# CONNECTORS.net
KiCad netlist of a schematic drawn in Altium Designer
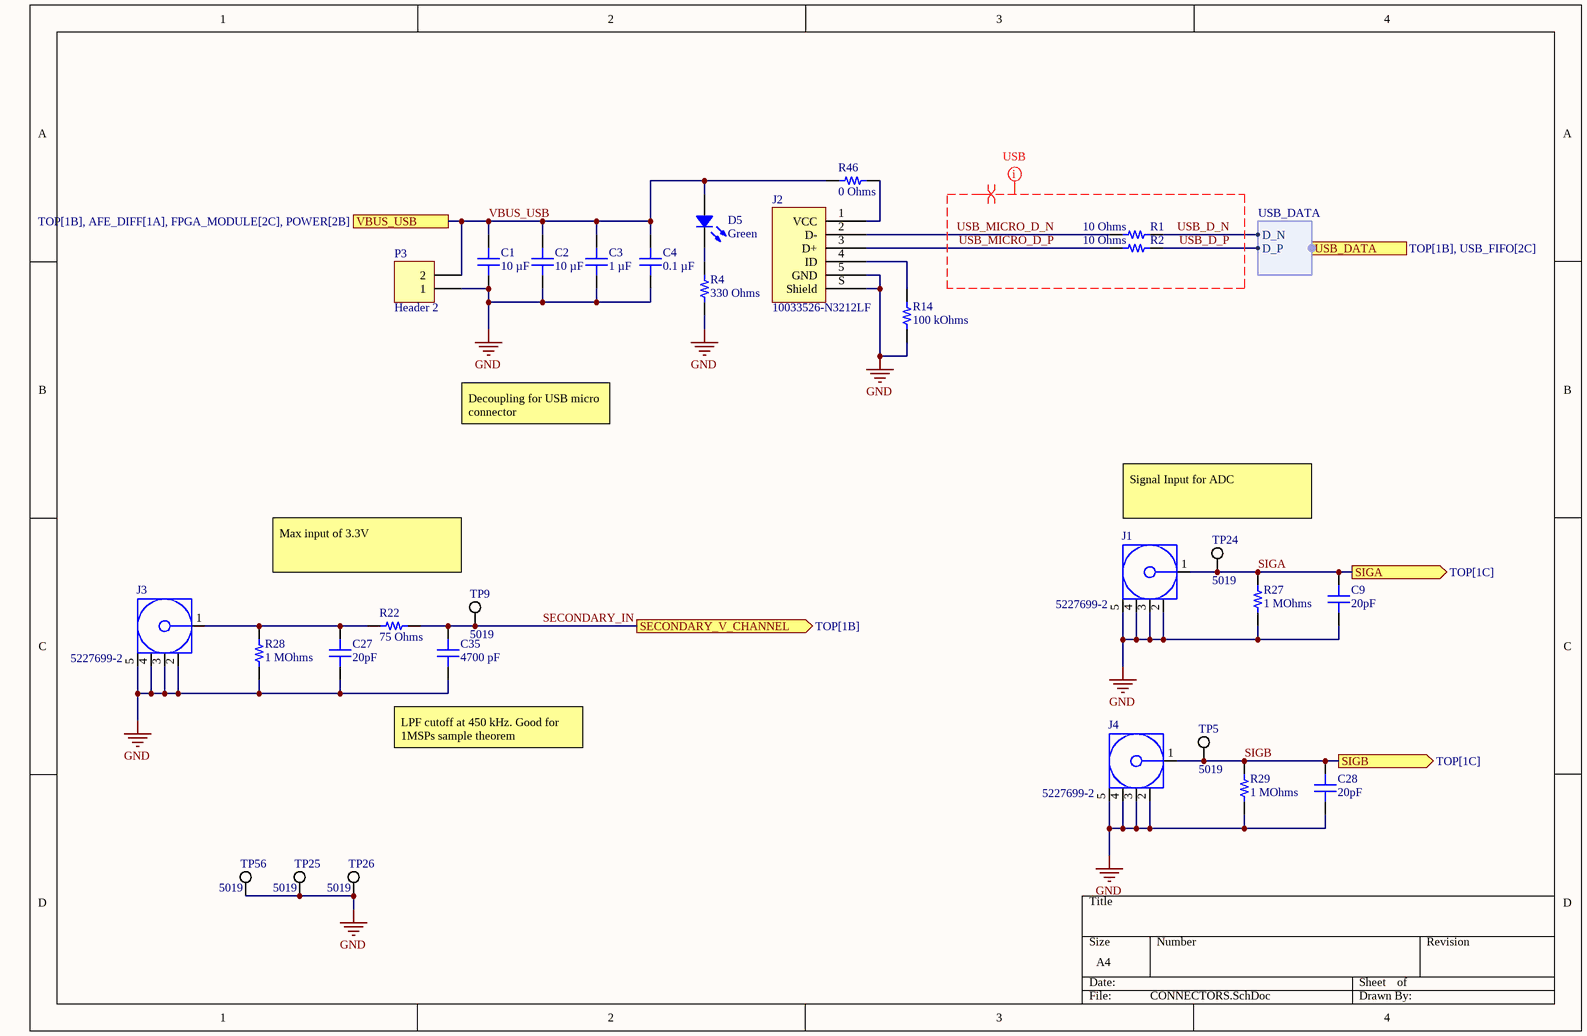
[diagram p0: CONNECTORS.SchDoc]

(export (version "E")
  (design (tool "Eeschema 10.0.6"))
  (components
    (comp (ref "C1")
      (value "10 µF")
      (footprint "CAP 0402_1005")
      (description "CAP CER 10UF 10V X5R 0402")
      (fields
        (field (name "PART NUMBER") "CL05A106MP8NUB8")
        (field (name "MANUFACTURER") "Samsung Electro-Mechanics")
      )
      (libsource (lib "Celestial") (part "Capacitor"))
    )
    (comp (ref "C2")
      (value "10 µF")
      (footprint "CAP 0402_1005")
      (description "CAP CER 10UF 10V X5R 0402")
      (fields
        (field (name "PART NUMBER") "CL05A106MP8NUB8")
        (field (name "MANUFACTURER") "Samsung Electro-Mechanics")
      )
      (libsource (lib "Celestial") (part "Capacitor"))
    )
    (comp (ref "C3")
      (value "1 µF")
      (footprint "CAP 0402_1005")
      (description "CAP CER 1UF 10V X7S 0402")
      (fields
        (field (name "PART NUMBER") "GRM155C71A105KE11D")
        (field (name "MANUFACTURER") "Murata Electronics")
      )
      (libsource (lib "Celestial") (part "Capacitor"))
    )
    (comp (ref "C4")
      (value "0.1 µF")
      (footprint "CAP 0402_1005")
      (description "CAP CER 0.1UF 50V X5R 0402")
      (fields
        (field (name "PART NUMBER") "CGA2B3X5R1H104M050BB")
        (field (name "MANUFACTURER") "TDK Corporation")
      )
      (libsource (lib "Celestial") (part "Capacitor"))
    )
    (comp (ref "C9")
      (value "20pF")
      (footprint "CAP 0402_1005")
      (description "CAP CER 20PF 25V NP0 0402")
      (fields (field (name "PART NUMBER") "04023U200JAT2A") (field (name "MANUFACTURER") "AVX Corporation"))
      (libsource (lib "Celestial") (part "Capacitor"))
    )
    (comp (ref "C27")
      (value "20pF")
      (footprint "CAP 0402_1005")
      (description "CAP CER 20PF 25V NP0 0402")
      (fields (field (name "PART NUMBER") "04023U200JAT2A") (field (name "MANUFACTURER") "AVX Corporation"))
      (libsource (lib "Celestial") (part "Capacitor"))
    )
    (comp (ref "C28")
      (value "20pF")
      (footprint "CAP 0402_1005")
      (description "CAP CER 20PF 25V NP0 0402")
      (fields (field (name "PART NUMBER") "04023U200JAT2A") (field (name "MANUFACTURER") "AVX Corporation"))
      (libsource (lib "Celestial") (part "Capacitor"))
    )
    (comp (ref "C35")
      (value "4700 pF")
      (footprint "CAP 0603_1608")
      (description "CAP CER 0603 4.7NF 16V X7R 10%")
      (fields (field (name "PART NUMBER") "C0603C472K4RECAUTO") (field (name "MANUFACTURER") "KEMET"))
      (libsource (lib "Celestial") (part "Capacitor"))
    )
    (comp (ref "D5")
      (value "Green")
      (footprint "LED 1206_3216 GREEN")
      (description "LED SMD")
      (fields (field (name "PART NUMBER") "APTL3216ZGCK-01") (field (name "MANUFACTURER") "Kingbright"))
      (libsource (lib "Celestial") (part "LED"))
    )
    (comp (ref "J1")
      (value "5227699-2")
      (footprint "TECO-5227699-2_V")
      (description "Jack BNC Connector, 1 Position, Height 16.26 mm, Tail Length 6.35 mm, -55 to 85 degC, RoHS, Tube")
      (fields (field (name "MANUFACTURER") "TE Connectivity"))
      (libsource (lib "Altium Content Vault") (part "CN-S-4F-RF5"))
    )
    (comp (ref "J2")
      (value "10033526-N3212LF")
      (footprint "FCI USB 10033526-N3212LF")
      (description "CONN RCPT MINI USB B 5POS SMD RA")
      (fields (field (name "MANUFACTURER") "Amphenol ICC (FCI)"))
      (libsource (lib "Celestial") (part "USB 2.0 Type B Micro"))
    )
    (comp (ref "J3")
      (value "5227699-2")
      (footprint "TECO-5227699-2_V")
      (description "Jack BNC Connector, 1 Position, Height 16.26 mm, Tail Length 6.35 mm, -55 to 85 degC, RoHS, Tube")
      (fields (field (name "MANUFACTURER") "TE Connectivity"))
      (libsource (lib "Altium Content Vault") (part "CN-S-4F-RF5"))
    )
    (comp (ref "J4")
      (value "5227699-2")
      (footprint "TECO-5227699-2_V")
      (description "Jack BNC Connector, 1 Position, Height 16.26 mm, Tail Length 6.35 mm, -55 to 85 degC, RoHS, Tube")
      (fields (field (name "MANUFACTURER") "TE Connectivity"))
      (libsource (lib "Altium Content Vault") (part "CN-S-4F-RF5"))
    )
    (comp (ref "P3")
      (value "Header 2")
      (footprint "HDR1X2")
      (description "Header, 2-Pin")
      (fields (field (name "PUBLISHER") "Altium Limited"))
      (libsource (lib "Miscellaneous Connectors") (part "Header 2"))
    )
    (comp (ref "R1")
      (value "10 Ohms")
      (footprint "RES 0603_1608")
      (description "RES SMD 10 OHM 0.1% 1/10W 0603")
      (fields (field (name "PART NUMBER") "CRT0603-BY-10R0ELF") (field (name "MANUFACTURER") "Bourns Inc."))
      (libsource (lib "Celestial") (part "Resistor"))
    )
    (comp (ref "R2")
      (value "10 Ohms")
      (footprint "RES 0603_1608")
      (description "RES SMD 10 OHM 0.1% 1/10W 0603")
      (fields (field (name "PART NUMBER") "CRT0603-BY-10R0ELF") (field (name "MANUFACTURER") "Bourns Inc."))
      (libsource (lib "Celestial") (part "Resistor"))
    )
    (comp (ref "R4")
      (value "330 Ohms")
      (footprint "RES 0402_1005")
      (description "RES SMD 330 OHM 5% 1/16W 0402")
      (fields (field (name "PART NUMBER") "AC0402JR-07330RL") (field (name "MANUFACTURER") "Yageo"))
      (libsource (lib "Celestial") (part "Resistor"))
    )
    (comp (ref "R14")
      (value "100 kOhms")
      (footprint "RES 0402_1005")
      (description "RES SMD 100K OHM 0.1% 1/16W 0402")
      (fields
        (field (name "PART NUMBER") "CPF0402B100KE")
        (field (name "MANUFACTURER") "TE Connectivity Passive Product")
      )
      (libsource (lib "Celestial") (part "Resistor"))
    )
    (comp (ref "R22")
      (value "75 Ohms")
      (footprint "RES 0603_1608")
      (description "RES SMD 75 OHM 1% 1/10W 0603")
      (fields (field (name "PART NUMBER") "AC0603FR-0775RL") (field (name "MANUFACTURER") "Yageo"))
      (libsource (lib "Celestial") (part "Resistor"))
    )
    (comp (ref "R27")
      (value "1 MOhms")
      (footprint "RES 0402_1005")
      (description "RES 1M OHM 1% 1/16W 0402")
      (fields
        (field (name "PART NUMBER") "RMCF0402FT1M00")
        (field (name "MANUFACTURER") "Stackpole Electronics Inc")
      )
      (libsource (lib "Celestial") (part "Resistor"))
    )
    (comp (ref "R28")
      (value "1 MOhms")
      (footprint "RES 0402_1005")
      (description "RES 1M OHM 1% 1/16W 0402")
      (fields
        (field (name "PART NUMBER") "RMCF0402FT1M00")
        (field (name "MANUFACTURER") "Stackpole Electronics Inc")
      )
      (libsource (lib "Celestial") (part "Resistor"))
    )
    (comp (ref "R29")
      (value "1 MOhms")
      (footprint "RES 0402_1005")
      (description "RES 1M OHM 1% 1/16W 0402")
      (fields
        (field (name "PART NUMBER") "RMCF0402FT1M00")
        (field (name "MANUFACTURER") "Stackpole Electronics Inc")
      )
      (libsource (lib "Celestial") (part "Resistor"))
    )
    (comp (ref "R46")
      (value "0 Ohms")
      (footprint "RES 0603_1608")
      (description "RES SMD 0 OHM JUMPER 1/2W 0603")
      (fields (field (name "PART NUMBER") "5110") (field (name "MANUFACTURER") "Keystone Electronics"))
      (libsource (lib "Celestial") (part "Resistor"))
    )
    (comp (ref "TP5")
      (value "5019")
      (footprint "KSTN-5019_V")
      (description "Test Point, 1 Position SMD, RoHS, Tape and Reel")
      (libsource (lib "Altium Content Vault") (part "TESTPOINT_WHITE"))
    )
    (comp (ref "TP9")
      (value "5019")
      (footprint "KSTN-5019_V")
      (description "Test Point, 1 Position SMD, RoHS, Tape and Reel")
      (libsource (lib "Altium Content Vault") (part "TESTPOINT_WHITE"))
    )
    (comp (ref "TP24")
      (value "5019")
      (footprint "KSTN-5019_V")
      (description "Test Point, 1 Position SMD, RoHS, Tape and Reel")
      (libsource (lib "Altium Content Vault") (part "TESTPOINT_WHITE"))
    )
    (comp (ref "TP25")
      (value "5019")
      (footprint "KSTN-5019_V")
      (description "Test Point, 1 Position SMD, RoHS, Tape and Reel")
      (libsource (lib "Altium Content Vault") (part "TESTPOINT_WHITE"))
    )
    (comp (ref "TP26")
      (value "5019")
      (footprint "KSTN-5019_V")
      (description "Test Point, 1 Position SMD, RoHS, Tape and Reel")
      (libsource (lib "Altium Content Vault") (part "TESTPOINT_WHITE"))
    )
    (comp (ref "TP56")
      (value "5019")
      (footprint "KSTN-5019_V")
      (description "Test Point, 1 Position SMD, RoHS, Tape and Reel")
      (libsource (lib "Altium Content Vault") (part "TESTPOINT_WHITE"))
    )
  )
  (nets
    (net (code "2") (name "/SECONDARY_IN") (class "Default")
      (node (ref "C35") (pin "2") (pinfunction "2_2") (pintype "passive"))
      (node (ref "R22") (pin "2") (pinfunction "2_2") (pintype "passive"))
      (node (ref "TP9") (pin "1") (pinfunction "1_1") (pintype "passive"))
    )
    (net (code "3") (name "/SIGA") (class "Default")
      (node (ref "C9") (pin "2") (pinfunction "2_2") (pintype "passive"))
      (node (ref "J1") (pin "1") (pinfunction "1_1") (pintype "passive"))
      (node (ref "R27") (pin "2") (pinfunction "2_2") (pintype "passive"))
      (node (ref "TP24") (pin "1") (pinfunction "1_1") (pintype "passive"))
    )
    (net (code "4") (name "/SIGB") (class "Default")
      (node (ref "C28") (pin "2") (pinfunction "2_2") (pintype "passive"))
      (node (ref "J4") (pin "1") (pinfunction "1_1") (pintype "passive"))
      (node (ref "R29") (pin "2") (pinfunction "2_2") (pintype "passive"))
      (node (ref "TP5") (pin "1") (pinfunction "1_1") (pintype "passive"))
    )
    (net (code "5") (name "/USB_D_N") (class "Default")
      (node (ref "R1") (pin "2") (pinfunction "2_2") (pintype "passive"))
    )
    (net (code "6") (name "/USB_D_P") (class "Default")
      (node (ref "R2") (pin "2") (pinfunction "2_2") (pintype "passive"))
    )
    (net (code "7") (name "/USB_MICRO_D_N") (class "Default")
      (node (ref "J2") (pin "2") (pinfunction "D-_2") (pintype "passive"))
      (node (ref "R1") (pin "1") (pinfunction "1_1") (pintype "passive"))
    )
    (net (code "8") (name "/USB_MICRO_D_P") (class "Default")
      (node (ref "J2") (pin "3") (pinfunction "D+_3") (pintype "passive"))
      (node (ref "R2") (pin "1") (pinfunction "1_1") (pintype "passive"))
    )
    (net (code "9") (name "/VBUS_USB") (class "Default")
      (node (ref "C1") (pin "2") (pinfunction "2_2") (pintype "passive"))
      (node (ref "C2") (pin "2") (pinfunction "2_2") (pintype "passive"))
      (node (ref "C3") (pin "2") (pinfunction "2_2") (pintype "passive"))
      (node (ref "C4") (pin "2") (pinfunction "2_2") (pintype "passive"))
      (node (ref "D5") (pin "1") (pinfunction "1_1") (pintype "passive"))
      (node (ref "P3") (pin "2") (pinfunction "2_2") (pintype "passive"))
      (node (ref "R46") (pin "2") (pinfunction "2_2") (pintype "passive"))
    )
    (net (code "11") (name "GND") (class "Default")
      (node (ref "C1") (pin "1") (pinfunction "1_1") (pintype "passive"))
      (node (ref "C2") (pin "1") (pinfunction "1_1") (pintype "passive"))
      (node (ref "C27") (pin "1") (pinfunction "1_1") (pintype "passive"))
      (node (ref "C28") (pin "1") (pinfunction "1_1") (pintype "passive"))
      (node (ref "C3") (pin "1") (pinfunction "1_1") (pintype "passive"))
      (node (ref "C35") (pin "1") (pinfunction "1_1") (pintype "passive"))
      (node (ref "C4") (pin "1") (pinfunction "1_1") (pintype "passive"))
      (node (ref "C9") (pin "1") (pinfunction "1_1") (pintype "passive"))
      (node (ref "J1") (pin "2") (pinfunction "2_2") (pintype "passive"))
      (node (ref "J1") (pin "3") (pinfunction "3_3") (pintype "passive"))
      (node (ref "J1") (pin "4") (pinfunction "4_4") (pintype "passive"))
      (node (ref "J1") (pin "5") (pinfunction "5_5") (pintype "passive"))
      (node (ref "J2") (pin "5") (pinfunction "GND_5") (pintype "passive"))
      (node (ref "J2") (pin "S") (pinfunction "Shield_S") (pintype "passive"))
      (node (ref "J3") (pin "2") (pinfunction "2_2") (pintype "passive"))
      (node (ref "J3") (pin "3") (pinfunction "3_3") (pintype "passive"))
      (node (ref "J3") (pin "4") (pinfunction "4_4") (pintype "passive"))
      (node (ref "J3") (pin "5") (pinfunction "5_5") (pintype "passive"))
      (node (ref "J4") (pin "2") (pinfunction "2_2") (pintype "passive"))
      (node (ref "J4") (pin "3") (pinfunction "3_3") (pintype "passive"))
      (node (ref "J4") (pin "4") (pinfunction "4_4") (pintype "passive"))
      (node (ref "J4") (pin "5") (pinfunction "5_5") (pintype "passive"))
      (node (ref "P3") (pin "1") (pinfunction "1_1") (pintype "passive"))
      (node (ref "R14") (pin "1") (pinfunction "1_1") (pintype "passive"))
      (node (ref "R27") (pin "1") (pinfunction "1_1") (pintype "passive"))
      (node (ref "R28") (pin "1") (pinfunction "1_1") (pintype "passive"))
      (node (ref "R29") (pin "1") (pinfunction "1_1") (pintype "passive"))
      (node (ref "R4") (pin "1") (pinfunction "1_1") (pintype "passive"))
      (node (ref "TP25") (pin "1") (pinfunction "1_1") (pintype "passive"))
      (node (ref "TP26") (pin "1") (pinfunction "1_1") (pintype "passive"))
      (node (ref "TP56") (pin "1") (pinfunction "1_1") (pintype "passive"))
    )
    (net (code "12") (name "Net-(C27-Pad2)") (class "Default")
      (node (ref "C27") (pin "2") (pinfunction "2_2") (pintype "passive"))
      (node (ref "J3") (pin "1") (pinfunction "1_1") (pintype "passive"))
      (node (ref "R22") (pin "1") (pinfunction "1_1") (pintype "passive"))
      (node (ref "R28") (pin "2") (pinfunction "2_2") (pintype "passive"))
    )
    (net (code "13") (name "Net-(D5-Pad2)") (class "Default")
      (node (ref "D5") (pin "2") (pinfunction "2_2") (pintype "passive"))
      (node (ref "R4") (pin "2") (pinfunction "2_2") (pintype "passive"))
    )
    (net (code "14") (name "Net-(J2-ID)") (class "Default")
      (node (ref "J2") (pin "4") (pinfunction "ID_4") (pintype "passive"))
      (node (ref "R14") (pin "2") (pinfunction "2_2") (pintype "passive"))
    )
    (net (code "15") (name "Net-(J2-VCC)") (class "Default")
      (node (ref "J2") (pin "1") (pinfunction "VCC_1") (pintype "passive"))
      (node (ref "R46") (pin "1") (pinfunction "1_1") (pintype "passive"))
    )
  )
)
